# working.net
KiCad netlist of a schematic drawn in EAGLE
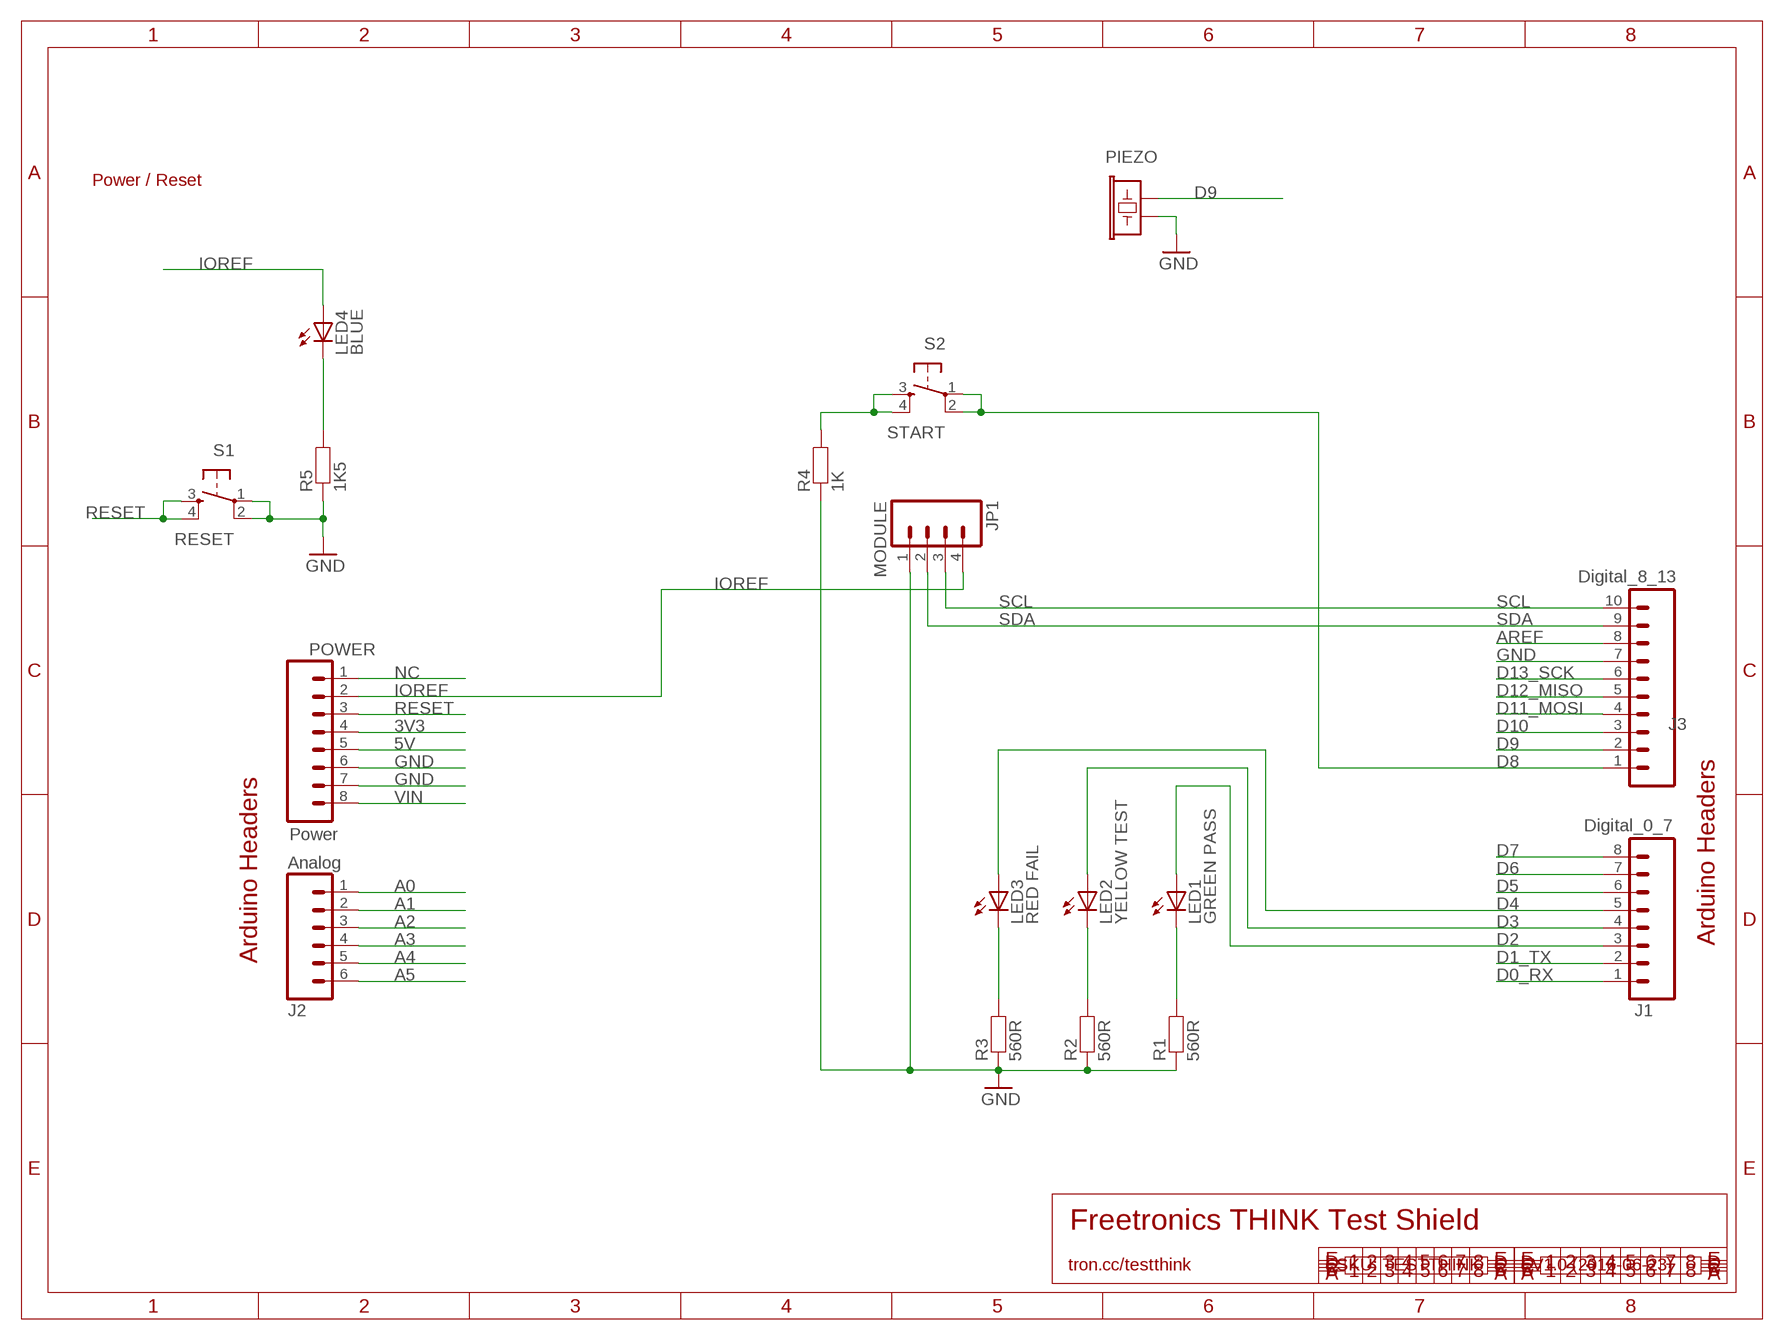
[diagram p0: schematic, sheet 1]

(export (version "E")
  (design (tool "Eeschema 10.0.6"))
  (components
    (comp (ref "J1")
      (value "Digital_0_7")
      (footprint "eagle-import:1X08")
      (libsource (lib "eagle-import") (part "M08"))
    )
    (comp (ref "J2")
      (value "Analog")
      (footprint "eagle-import:1X06")
      (libsource (lib "eagle-import") (part "M06SIP"))
    )
    (comp (ref "J3")
      (value "Digital_8_13")
      (footprint "eagle-import:1X10")
      (libsource (lib "eagle-import") (part "M100.1"))
    )
    (comp (ref "JP1")
      (value "MODULE")
      (footprint "eagle-import:1X04")
      (libsource (lib "eagle-import") (part "M04PTH"))
    )
    (comp (ref "LED1")
      (value "GREEN PASS")
      (footprint "eagle-import:LED-0603")
      (libsource (lib "eagle-import") (part "LED0603"))
    )
    (comp (ref "LED2")
      (value "YELLOW TEST")
      (footprint "eagle-import:LED-0603")
      (libsource (lib "eagle-import") (part "LED0603"))
    )
    (comp (ref "LED3")
      (value "RED FAIL")
      (footprint "eagle-import:LED-0603")
      (libsource (lib "eagle-import") (part "LED0603"))
    )
    (comp (ref "LED4")
      (value "BLUE")
      (footprint "eagle-import:LED-0603")
      (libsource (lib "eagle-import") (part "LED0603"))
    )
    (comp (ref "PIEZO")
      (value "BUZZERSMD12X12")
      (footprint "eagle-import:BUZZER-12X12-SMT")
      (libsource (lib "eagle-import") (part "BUZZERSMD12X12"))
    )
    (comp (ref "POWER")
      (value "Power")
      (footprint "eagle-import:1X08")
      (libsource (lib "eagle-import") (part "M08"))
    )
    (comp (ref "R1")
      (value "560R")
      (footprint "eagle-import:0603")
      (libsource (lib "eagle-import") (part "RESISTOR0603"))
    )
    (comp (ref "R2")
      (value "560R")
      (footprint "eagle-import:0603")
      (libsource (lib "eagle-import") (part "RESISTOR0603"))
    )
    (comp (ref "R3")
      (value "560R")
      (footprint "eagle-import:0603")
      (libsource (lib "eagle-import") (part "RESISTOR0603"))
    )
    (comp (ref "R4")
      (value "1K")
      (footprint "eagle-import:0603")
      (libsource (lib "eagle-import") (part "RESISTOR0603"))
    )
    (comp (ref "R5")
      (value "1K5")
      (footprint "eagle-import:0603")
      (libsource (lib "eagle-import") (part "RESISTOR0603"))
    )
    (comp (ref "S1")
      (value "RESET")
      (footprint "eagle-import:TACTILE-PTH")
      (libsource (lib "eagle-import") (part "TAC_SWITCHPTH"))
    )
    (comp (ref "S2")
      (value "START")
      (footprint "eagle-import:TACTILE-PTH")
      (libsource (lib "eagle-import") (part "TAC_SWITCHPTH"))
    )
  )
  (nets
    (net (code "1") (name "/3V3") (class "Default")
      (node (ref "POWER") (pin "4") (pinfunction "4_4") (pintype "passive"))
    )
    (net (code "2") (name "/5V") (class "Default")
      (node (ref "POWER") (pin "5") (pinfunction "5_5") (pintype "passive"))
    )
    (net (code "3") (name "/A0") (class "Default")
      (node (ref "J2") (pin "1") (pinfunction "1_1") (pintype "passive"))
    )
    (net (code "4") (name "/A1") (class "Default")
      (node (ref "J2") (pin "2") (pinfunction "2_2") (pintype "passive"))
    )
    (net (code "5") (name "/A2") (class "Default")
      (node (ref "J2") (pin "3") (pinfunction "3_3") (pintype "passive"))
    )
    (net (code "6") (name "/A3") (class "Default")
      (node (ref "J2") (pin "4") (pinfunction "4_4") (pintype "passive"))
    )
    (net (code "7") (name "/A4") (class "Default")
      (node (ref "J2") (pin "5") (pinfunction "5_5") (pintype "passive"))
    )
    (net (code "8") (name "/A5") (class "Default")
      (node (ref "J2") (pin "6") (pinfunction "6_6") (pintype "passive"))
    )
    (net (code "9") (name "/AREF") (class "Default")
      (node (ref "J3") (pin "8") (pinfunction "8_8") (pintype "passive"))
    )
    (net (code "10") (name "/D0_RX") (class "Default")
      (node (ref "J1") (pin "1") (pinfunction "1_1") (pintype "passive"))
    )
    (net (code "11") (name "/D1_TX") (class "Default")
      (node (ref "J1") (pin "2") (pinfunction "2_2") (pintype "passive"))
    )
    (net (code "12") (name "/D2") (class "Default")
      (node (ref "J1") (pin "3") (pinfunction "3_3") (pintype "passive"))
      (node (ref "LED1") (pin "A") (pinfunction "A_A") (pintype "passive"))
    )
    (net (code "13") (name "/D3") (class "Default")
      (node (ref "J1") (pin "4") (pinfunction "4_4") (pintype "passive"))
      (node (ref "LED2") (pin "A") (pinfunction "A_A") (pintype "passive"))
    )
    (net (code "14") (name "/D4") (class "Default")
      (node (ref "J1") (pin "5") (pinfunction "5_5") (pintype "passive"))
      (node (ref "LED3") (pin "A") (pinfunction "A_A") (pintype "passive"))
    )
    (net (code "15") (name "/D5") (class "Default")
      (node (ref "J1") (pin "6") (pinfunction "6_6") (pintype "passive"))
    )
    (net (code "16") (name "/D6") (class "Default")
      (node (ref "J1") (pin "7") (pinfunction "7_7") (pintype "passive"))
    )
    (net (code "17") (name "/D7") (class "Default")
      (node (ref "J1") (pin "8") (pinfunction "8_8") (pintype "passive"))
    )
    (net (code "18") (name "/D8") (class "Default")
      (node (ref "J3") (pin "1") (pinfunction "1_1") (pintype "passive"))
      (node (ref "S2") (pin "1") (pinfunction "1_1") (pintype "passive"))
      (node (ref "S2") (pin "2") (pinfunction "2_2") (pintype "passive"))
    )
    (net (code "19") (name "/D9") (class "Default")
      (node (ref "J3") (pin "2") (pinfunction "2_2") (pintype "passive"))
      (node (ref "PIEZO") (pin "2") (pinfunction "2_2") (pintype "passive"))
    )
    (net (code "20") (name "/D10") (class "Default")
      (node (ref "J3") (pin "3") (pinfunction "3_3") (pintype "passive"))
    )
    (net (code "21") (name "/D11_MOSI") (class "Default")
      (node (ref "J3") (pin "4") (pinfunction "4_4") (pintype "passive"))
    )
    (net (code "22") (name "/D12_MISO") (class "Default")
      (node (ref "J3") (pin "5") (pinfunction "5_5") (pintype "passive"))
    )
    (net (code "23") (name "/D13_SCK") (class "Default")
      (node (ref "J3") (pin "6") (pinfunction "6_6") (pintype "passive"))
    )
    (net (code "24") (name "/IOREF") (class "Default")
      (node (ref "JP1") (pin "4") (pinfunction "4_4") (pintype "passive"))
      (node (ref "LED4") (pin "A") (pinfunction "A_A") (pintype "passive"))
      (node (ref "POWER") (pin "2") (pinfunction "2_2") (pintype "passive"))
    )
    (net (code "25") (name "/NC") (class "Default")
      (node (ref "POWER") (pin "1") (pinfunction "1_1") (pintype "passive"))
    )
    (net (code "26") (name "/RESET") (class "Default")
      (node (ref "POWER") (pin "3") (pinfunction "3_3") (pintype "passive"))
      (node (ref "S1") (pin "3") (pinfunction "3_3") (pintype "passive"))
      (node (ref "S1") (pin "4") (pinfunction "4_4") (pintype "passive"))
    )
    (net (code "27") (name "/SCL") (class "Default")
      (node (ref "J3") (pin "10") (pinfunction "10_10") (pintype "passive"))
      (node (ref "JP1") (pin "3") (pinfunction "3_3") (pintype "passive"))
    )
    (net (code "28") (name "/SDA") (class "Default")
      (node (ref "J3") (pin "9") (pinfunction "9_9") (pintype "passive"))
      (node (ref "JP1") (pin "2") (pinfunction "2_2") (pintype "passive"))
    )
    (net (code "29") (name "/VIN") (class "Default")
      (node (ref "POWER") (pin "8") (pinfunction "8_8") (pintype "passive"))
    )
    (net (code "30") (name "GND") (class "Default")
      (node (ref "J3") (pin "7") (pinfunction "7_7") (pintype "passive"))
      (node (ref "JP1") (pin "1") (pinfunction "1_1") (pintype "passive"))
      (node (ref "PIEZO") (pin "1") (pinfunction "1_1") (pintype "passive"))
      (node (ref "POWER") (pin "6") (pinfunction "6_6") (pintype "passive"))
      (node (ref "POWER") (pin "7") (pinfunction "7_7") (pintype "passive"))
      (node (ref "R1") (pin "1") (pinfunction "1_1") (pintype "passive"))
      (node (ref "R2") (pin "1") (pinfunction "1_1") (pintype "passive"))
      (node (ref "R3") (pin "1") (pinfunction "1_1") (pintype "passive"))
      (node (ref "R4") (pin "1") (pinfunction "1_1") (pintype "passive"))
      (node (ref "R5") (pin "1") (pinfunction "1_1") (pintype "passive"))
      (node (ref "S1") (pin "1") (pinfunction "1_1") (pintype "passive"))
      (node (ref "S1") (pin "2") (pinfunction "2_2") (pintype "passive"))
    )
    (net (code "31") (name "Net-(LED1-PadC)") (class "Default")
      (node (ref "LED1") (pin "C") (pinfunction "C_C") (pintype "passive"))
      (node (ref "R1") (pin "2") (pinfunction "2_2") (pintype "passive"))
    )
    (net (code "32") (name "Net-(LED2-PadC)") (class "Default")
      (node (ref "LED2") (pin "C") (pinfunction "C_C") (pintype "passive"))
      (node (ref "R2") (pin "2") (pinfunction "2_2") (pintype "passive"))
    )
    (net (code "33") (name "Net-(LED3-PadC)") (class "Default")
      (node (ref "LED3") (pin "C") (pinfunction "C_C") (pintype "passive"))
      (node (ref "R3") (pin "2") (pinfunction "2_2") (pintype "passive"))
    )
    (net (code "34") (name "Net-(LED4-PadC)") (class "Default")
      (node (ref "LED4") (pin "C") (pinfunction "C_C") (pintype "passive"))
      (node (ref "R5") (pin "2") (pinfunction "2_2") (pintype "passive"))
    )
    (net (code "35") (name "Net-(R4-Pad2)") (class "Default")
      (node (ref "R4") (pin "2") (pinfunction "2_2") (pintype "passive"))
      (node (ref "S2") (pin "3") (pinfunction "3_3") (pintype "passive"))
      (node (ref "S2") (pin "4") (pinfunction "4_4") (pintype "passive"))
    )
  )
)
